# ESP8266_dev.net
KiCad netlist of a schematic drawn in EAGLE
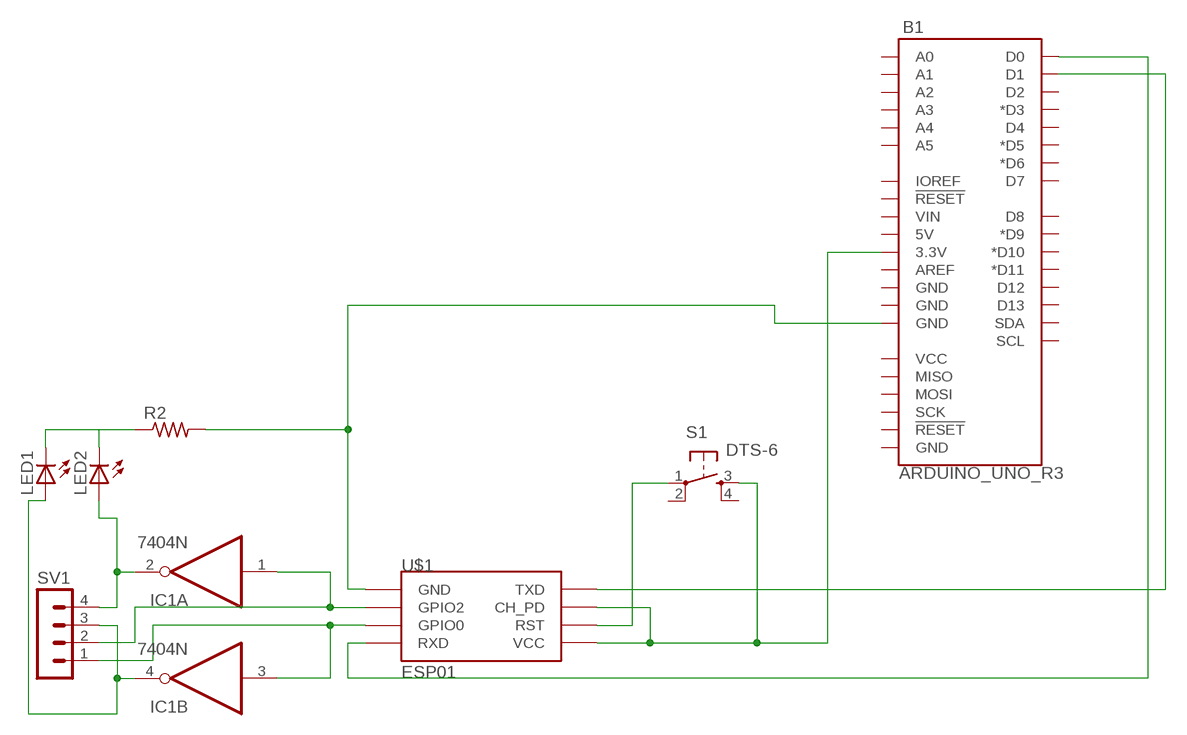
[diagram p0: schematic, sheet 1]

(export (version "E")
  (design (tool "Eeschema 10.0.6"))
  (components
    (comp (ref "B1")
      (value "ARDUINO_UNO_R3")
      (footprint "eagle-import:ARDUINO_R3")
      (libsource (lib "eagle-import") (part "ARDUINO_UNO_R3"))
    )
    (comp (ref "IC1")
      (value "7404N")
      (footprint "eagle-import:DIL14")
      (libsource (lib "eagle-import") (part "7404N"))
    )
    (comp (ref "LED1")
      (value "LED3MM")
      (footprint "eagle-import:LED3MM")
      (libsource (lib "eagle-import") (part "LED3MM"))
    )
    (comp (ref "LED2")
      (value "LED3MM")
      (footprint "eagle-import:LED3MM")
      (libsource (lib "eagle-import") (part "LED3MM"))
    )
    (comp (ref "R2")
      (value "R-US_0207/15")
      (footprint "eagle-import:0207_15")
      (libsource (lib "eagle-import") (part "R-US_0207/15"))
    )
    (comp (ref "S1")
      (value "DTS-6")
      (footprint "eagle-import:DTS-6")
      (libsource (lib "eagle-import") (part "DTS-6"))
    )
    (comp (ref "SV1")
      (value "MA04-1")
      (footprint "eagle-import:MA04-1")
      (libsource (lib "eagle-import") (part "MA04-1"))
    )
    (comp (ref "U$1")
      (value "ESP01")
      (footprint "eagle-import:ESP01")
      (libsource (lib "eagle-import") (part "ESP01"))
    )
  )
  (nets
    (net (code "1") (name "Net-(B1-GND-PadGND@2)") (class "Default")
      (node (ref "B1") (pin "GND@2") (pinfunction "GND_GND@2") (pintype "bidirectional"))
      (node (ref "R2") (pin "2") (pinfunction "2_2") (pintype "passive"))
      (node (ref "U$1") (pin "GND") (pinfunction "GND_GND") (pintype "bidirectional"))
    )
    (net (code "2") (name "Net-(B1-Pad3.3V)") (class "Default")
      (node (ref "B1") (pin "3.3V") (pinfunction "3.3V_3.3V") (pintype "bidirectional"))
      (node (ref "S1") (pin "3") (pinfunction "3_3") (pintype "passive"))
      (node (ref "U$1") (pin "CH_PD") (pinfunction "CH_PD_CH_PD") (pintype "bidirectional"))
      (node (ref "U$1") (pin "VCC") (pinfunction "VCC_VCC") (pintype "bidirectional"))
    )
    (net (code "3") (name "Net-(IC1A-I)") (class "Default")
      (node (ref "IC1") (pin "1") (pinfunction "I_1") (pintype "input"))
      (node (ref "SV1") (pin "2") (pinfunction "2_2") (pintype "passive"))
      (node (ref "U$1") (pin "GPIO2") (pinfunction "GPIO2_GPIO2") (pintype "bidirectional"))
    )
    (net (code "4") (name "Net-(IC1A-O)") (class "Default")
      (node (ref "IC1") (pin "2") (pinfunction "O_2") (pintype "output"))
      (node (ref "LED2") (pin "A") (pinfunction "A_A") (pintype "passive"))
      (node (ref "SV1") (pin "4") (pinfunction "4_4") (pintype "passive"))
    )
    (net (code "5") (name "Net-(IC1B-I)") (class "Default")
      (node (ref "IC1") (pin "3") (pinfunction "I_3") (pintype "input"))
      (node (ref "SV1") (pin "1") (pinfunction "1_1") (pintype "passive"))
      (node (ref "U$1") (pin "GPIO0") (pinfunction "GPIO0_GPIO0") (pintype "bidirectional"))
    )
    (net (code "6") (name "Net-(IC1B-O)") (class "Default")
      (node (ref "IC1") (pin "4") (pinfunction "O_4") (pintype "output"))
      (node (ref "LED1") (pin "A") (pinfunction "A_A") (pintype "passive"))
      (node (ref "SV1") (pin "3") (pinfunction "3_3") (pintype "passive"))
    )
    (net (code "7") (name "Net-(LED1-C)") (class "Default")
      (node (ref "LED1") (pin "K") (pinfunction "C_K") (pintype "passive"))
      (node (ref "LED2") (pin "K") (pinfunction "C_K") (pintype "passive"))
      (node (ref "R2") (pin "1") (pinfunction "1_1") (pintype "passive"))
    )
    (net (code "8") (name "Net-(S1-Pad1)") (class "Default")
      (node (ref "S1") (pin "1") (pinfunction "1_1") (pintype "passive"))
      (node (ref "U$1") (pin "RST") (pinfunction "RST_RST") (pintype "bidirectional"))
    )
    (net (code "9") (name "Net-(U$1-RXD)") (class "Default")
      (node (ref "B1") (pin "D0") (pinfunction "D0_D0") (pintype "bidirectional"))
      (node (ref "U$1") (pin "RX") (pinfunction "RXD_RX") (pintype "bidirectional"))
    )
    (net (code "10") (name "Net-(U$1-TXD)") (class "Default")
      (node (ref "B1") (pin "D1") (pinfunction "D1_D1") (pintype "bidirectional"))
      (node (ref "U$1") (pin "TX") (pinfunction "TXD_TX") (pintype "bidirectional"))
    )
    (net (code "11") (name "unconnected-(B1-*D3-PadD3)") (class "Default")
      (node (ref "B1") (pin "D3") (pinfunction "*D3_D3") (pintype "bidirectional"))
    )
    (net (code "12") (name "unconnected-(B1-*D5-PadD5)") (class "Default")
      (node (ref "B1") (pin "D5") (pinfunction "*D5_D5") (pintype "bidirectional"))
    )
    (net (code "13") (name "unconnected-(B1-*D6-PadD6)") (class "Default")
      (node (ref "B1") (pin "D6") (pinfunction "*D6_D6") (pintype "bidirectional"))
    )
    (net (code "14") (name "unconnected-(B1-*D9-PadD9)") (class "Default")
      (node (ref "B1") (pin "D9") (pinfunction "*D9_D9") (pintype "bidirectional"))
    )
    (net (code "15") (name "unconnected-(B1-*D10-PadD10)") (class "Default")
      (node (ref "B1") (pin "D10") (pinfunction "*D10_D10") (pintype "bidirectional"))
    )
    (net (code "16") (name "unconnected-(B1-*D11-PadD11)") (class "Default")
      (node (ref "B1") (pin "D11") (pinfunction "*D11_D11") (pintype "bidirectional"))
    )
    (net (code "17") (name "unconnected-(B1-GND-PadGND@1)") (class "Default")
      (node (ref "B1") (pin "GND@1") (pinfunction "GND_GND@1") (pintype "bidirectional"))
    )
    (net (code "18") (name "unconnected-(B1-GND-PadGND@3)") (class "Default")
      (node (ref "B1") (pin "GND@3") (pinfunction "GND_GND@3") (pintype "bidirectional"))
    )
    (net (code "19") (name "unconnected-(B1-GND-PadGND@4)") (class "Default")
      (node (ref "B1") (pin "GND@4") (pinfunction "GND_GND@4") (pintype "bidirectional"))
    )
    (net (code "20") (name "unconnected-(B1-Pad5V)") (class "Default")
      (node (ref "B1") (pin "5V") (pinfunction "5V_5V") (pintype "bidirectional"))
    )
    (net (code "21") (name "unconnected-(B1-PadA0)") (class "Default")
      (node (ref "B1") (pin "A0") (pinfunction "A0_A0") (pintype "bidirectional"))
    )
    (net (code "22") (name "unconnected-(B1-PadA1)") (class "Default")
      (node (ref "B1") (pin "A1") (pinfunction "A1_A1") (pintype "bidirectional"))
    )
    (net (code "23") (name "unconnected-(B1-PadA2)") (class "Default")
      (node (ref "B1") (pin "A2") (pinfunction "A2_A2") (pintype "bidirectional"))
    )
    (net (code "24") (name "unconnected-(B1-PadA3)") (class "Default")
      (node (ref "B1") (pin "A3") (pinfunction "A3_A3") (pintype "bidirectional"))
    )
    (net (code "25") (name "unconnected-(B1-PadA4)") (class "Default")
      (node (ref "B1") (pin "A4") (pinfunction "A4_A4") (pintype "bidirectional"))
    )
    (net (code "26") (name "unconnected-(B1-PadA5)") (class "Default")
      (node (ref "B1") (pin "A5") (pinfunction "A5_A5") (pintype "bidirectional"))
    )
    (net (code "27") (name "unconnected-(B1-PadAREF)") (class "Default")
      (node (ref "B1") (pin "AREF") (pinfunction "AREF_AREF") (pintype "bidirectional"))
    )
    (net (code "28") (name "unconnected-(B1-PadD2)") (class "Default")
      (node (ref "B1") (pin "D2") (pinfunction "D2_D2") (pintype "bidirectional"))
    )
    (net (code "29") (name "unconnected-(B1-PadD4)") (class "Default")
      (node (ref "B1") (pin "D4") (pinfunction "D4_D4") (pintype "bidirectional"))
    )
    (net (code "30") (name "unconnected-(B1-PadD7)") (class "Default")
      (node (ref "B1") (pin "D7") (pinfunction "D7_D7") (pintype "bidirectional"))
    )
    (net (code "31") (name "unconnected-(B1-PadD8)") (class "Default")
      (node (ref "B1") (pin "D8") (pinfunction "D8_D8") (pintype "bidirectional"))
    )
    (net (code "32") (name "unconnected-(B1-PadD12)") (class "Default")
      (node (ref "B1") (pin "D12") (pinfunction "D12_D12") (pintype "bidirectional"))
    )
    (net (code "33") (name "unconnected-(B1-PadD13)") (class "Default")
      (node (ref "B1") (pin "D13") (pinfunction "D13_D13") (pintype "bidirectional"))
    )
    (net (code "34") (name "unconnected-(B1-PadIOREF)") (class "Default")
      (node (ref "B1") (pin "IOREF") (pinfunction "IOREF_IOREF") (pintype "bidirectional"))
    )
    (net (code "35") (name "unconnected-(B1-PadMISO)") (class "Default")
      (node (ref "B1") (pin "MISO") (pinfunction "MISO_MISO") (pintype "bidirectional"))
    )
    (net (code "36") (name "unconnected-(B1-PadMOSI)") (class "Default")
      (node (ref "B1") (pin "MOSI") (pinfunction "MOSI_MOSI") (pintype "bidirectional"))
    )
    (net (code "37") (name "unconnected-(B1-PadSCK)") (class "Default")
      (node (ref "B1") (pin "SCK") (pinfunction "SCK_SCK") (pintype "bidirectional"))
    )
    (net (code "38") (name "unconnected-(B1-PadSCL)") (class "Default")
      (node (ref "B1") (pin "SCL") (pinfunction "SCL_SCL") (pintype "bidirectional"))
    )
    (net (code "39") (name "unconnected-(B1-PadSDA)") (class "Default")
      (node (ref "B1") (pin "SDA") (pinfunction "SDA_SDA") (pintype "bidirectional"))
    )
    (net (code "40") (name "unconnected-(B1-PadVCC)") (class "Default")
      (node (ref "B1") (pin "VCC") (pinfunction "VCC_VCC") (pintype "bidirectional"))
    )
    (net (code "41") (name "unconnected-(B1-PadVIN)") (class "Default")
      (node (ref "B1") (pin "VIN") (pinfunction "VIN_VIN") (pintype "bidirectional"))
    )
    (net (code "42") (name "unconnected-(B1-~{RESET}-PadRESET@1)") (class "Default")
      (node (ref "B1") (pin "RESET@1") (pinfunction "~{RESET}_RESET@1") (pintype "bidirectional"))
    )
    (net (code "43") (name "unconnected-(B1-~{RESET}-PadRESET@2)") (class "Default")
      (node (ref "B1") (pin "RESET@2") (pinfunction "~{RESET}_RESET@2") (pintype "bidirectional"))
    )
    (net (code "44") (name "unconnected-(S1-Pad2)") (class "Default")
      (node (ref "S1") (pin "2") (pinfunction "2_2") (pintype "passive"))
    )
    (net (code "45") (name "unconnected-(S1-Pad4)") (class "Default")
      (node (ref "S1") (pin "4") (pinfunction "4_4") (pintype "passive"))
    )
  )
)
